# P06_MODEM.net
KiCad netlist of a schematic drawn in EasyEDA
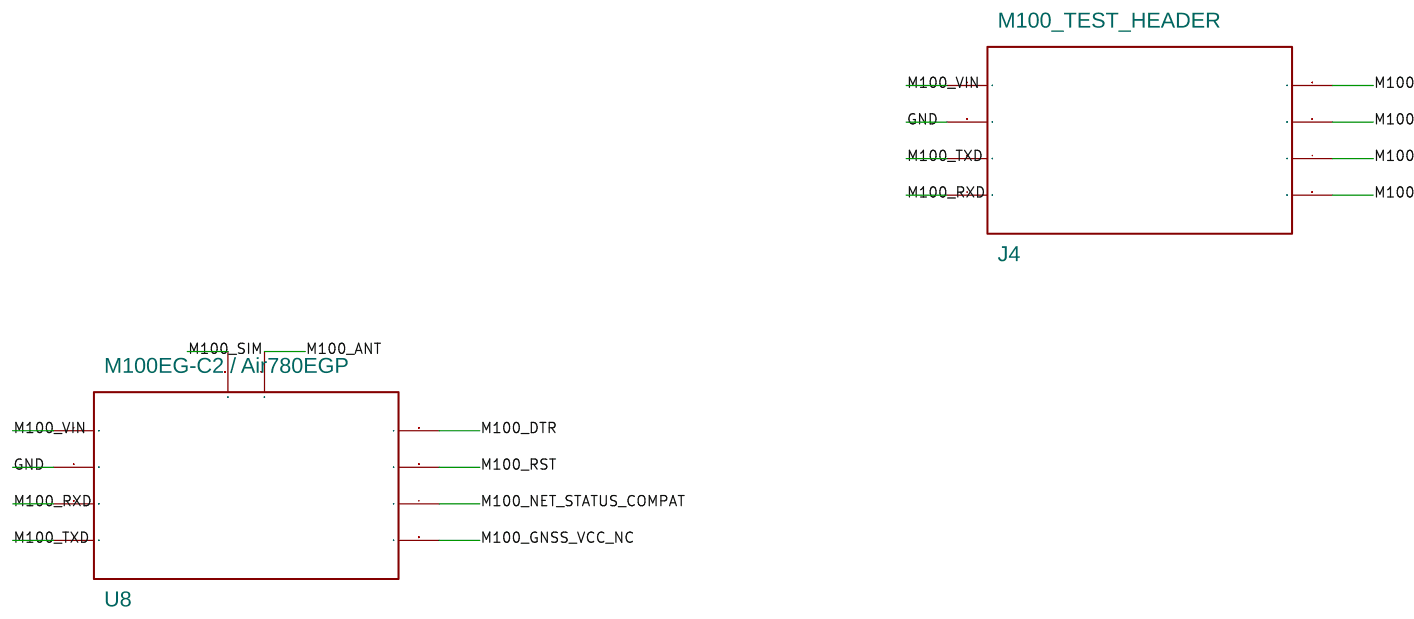
[diagram p0: schematic sheet]

(export (version "E")
  (design (tool "Eeschema 10.0.6"))
  (components
    (comp (ref "J4") (value "M100_TEST_HEADER") (libsource (lib "") (part "Test_Header")))
    (comp (ref "U8") (value "M100EG-C2 / Air780EGP") (libsource (lib "") (part "Air780EGP_Carrier")))
  )
  (nets
    (net (code "1") (name "/GND") (class "Default")
      (node (ref "J4") (pin "2") (pinfunction "1_2") (pintype "unspecified"))
      (node (ref "U8") (pin "2") (pinfunction "1_2") (pintype "unspecified"))
    )
    (net (code "2") (name "/M100_ANT") (class "Default")
      (node (ref "U8") (pin "10") (pinfunction "1_10") (pintype "unspecified"))
    )
    (net (code "3") (name "/M100_DTR") (class "Default")
      (node (ref "J4") (pin "5") (pinfunction "1_5") (pintype "unspecified"))
      (node (ref "U8") (pin "5") (pinfunction "1_5") (pintype "unspecified"))
    )
    (net (code "4") (name "/M100_GNSS_VCC_NC") (class "Default")
      (node (ref "J4") (pin "8") (pinfunction "1_8") (pintype "unspecified"))
      (node (ref "U8") (pin "8") (pinfunction "1_8") (pintype "unspecified"))
    )
    (net (code "5") (name "/M100_NET_STATUS_COMPAT") (class "Default")
      (node (ref "J4") (pin "7") (pinfunction "1_7") (pintype "unspecified"))
      (node (ref "U8") (pin "7") (pinfunction "1_7") (pintype "unspecified"))
    )
    (net (code "6") (name "/M100_RST") (class "Default")
      (node (ref "J4") (pin "6") (pinfunction "1_6") (pintype "unspecified"))
      (node (ref "U8") (pin "6") (pinfunction "1_6") (pintype "unspecified"))
    )
    (net (code "7") (name "/M100_RXD") (class "Default")
      (node (ref "J4") (pin "4") (pinfunction "1_4") (pintype "unspecified"))
      (node (ref "U8") (pin "3") (pinfunction "1_3") (pintype "unspecified"))
    )
    (net (code "8") (name "/M100_SIM") (class "Default")
      (node (ref "U8") (pin "9") (pinfunction "1_9") (pintype "unspecified"))
    )
    (net (code "9") (name "/M100_TXD") (class "Default")
      (node (ref "J4") (pin "3") (pinfunction "1_3") (pintype "unspecified"))
      (node (ref "U8") (pin "4") (pinfunction "1_4") (pintype "unspecified"))
    )
    (net (code "10") (name "/M100_VIN") (class "Default")
      (node (ref "J4") (pin "1") (pinfunction "1_1") (pintype "unspecified"))
      (node (ref "U8") (pin "1") (pinfunction "1_1") (pintype "unspecified"))
    )
  )
)
